# xmax_neopixel.net
KiCad netlist of a schematic drawn in EAGLE
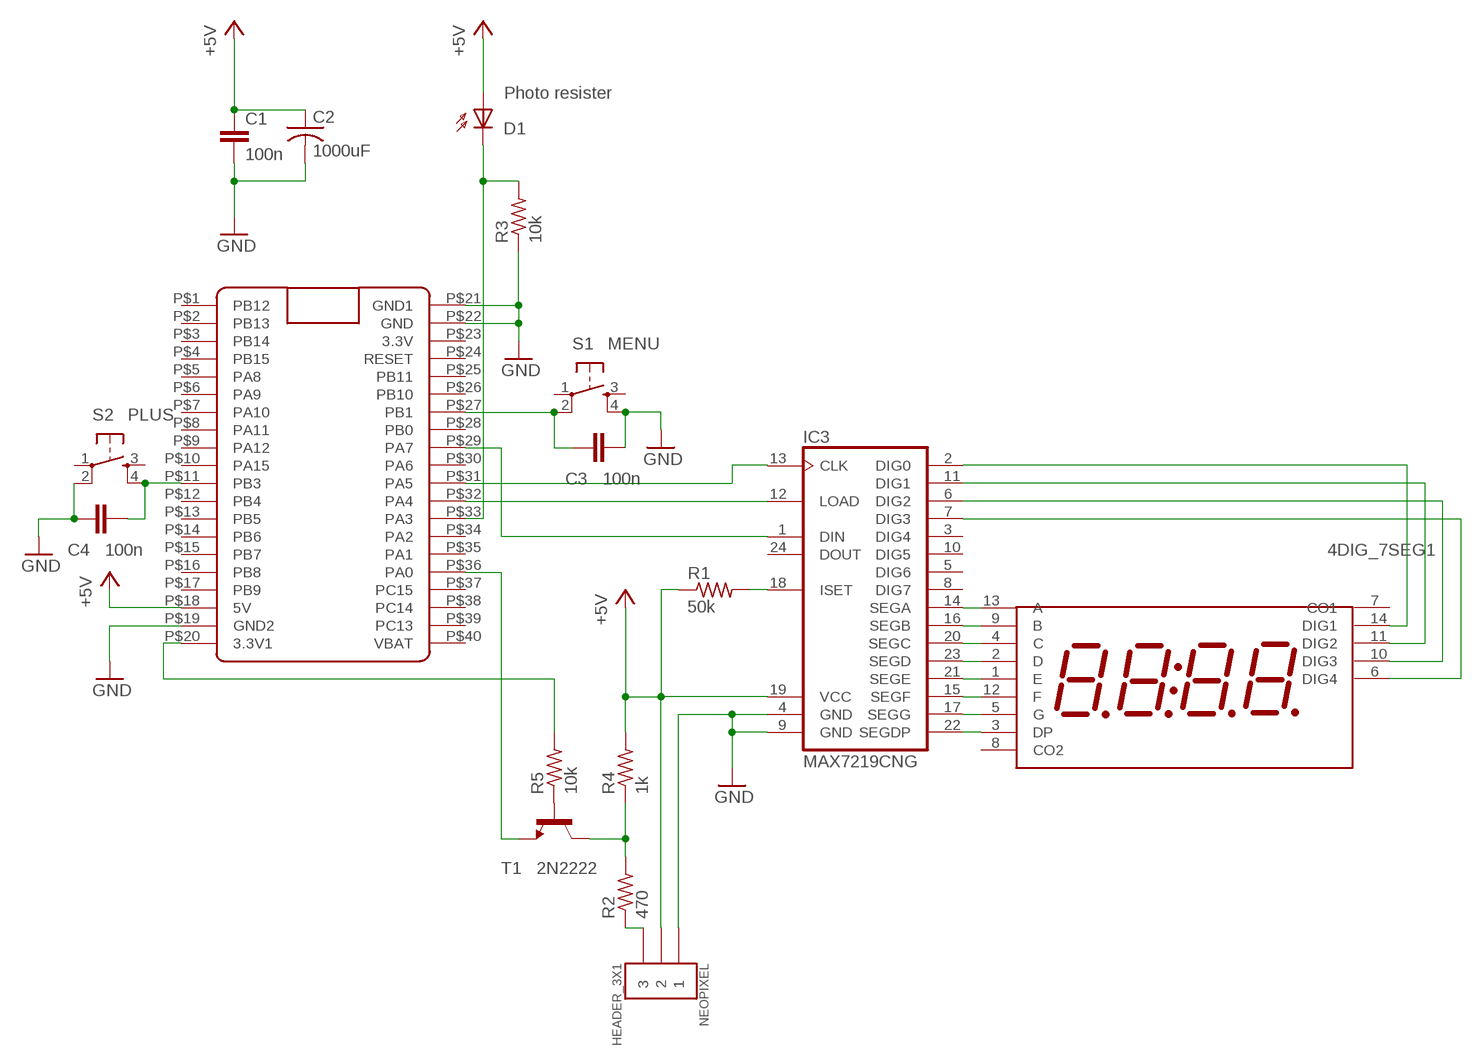
[diagram p0: schematic, sheet 1]

(export (version "E")
  (design (tool "Eeschema 10.0.6"))
  (components
    (comp (ref "4DIG_7SEG1")
      (value "4DIG_7SEG")
      (footprint "eagle-import:4DIG_7SEG")
      (libsource (lib "eagle-import") (part "4DIG_7SEG"))
    )
    (comp (ref "C1")
      (value "100n")
      (footprint "eagle-import:C025-024X044")
      (libsource (lib "eagle-import") (part "C-EU025-024X044"))
    )
    (comp (ref "C2")
      (value "1000uF")
      (footprint "eagle-import:C025-024X044")
      (libsource (lib "eagle-import") (part "C-US025-024X044"))
    )
    (comp (ref "C3")
      (value "100n")
      (footprint "eagle-import:C025-024X044")
      (libsource (lib "eagle-import") (part "C-EU025-024X044"))
    )
    (comp (ref "C4")
      (value "100n")
      (footprint "eagle-import:C025-024X044")
      (libsource (lib "eagle-import") (part "C-EU025-024X044"))
    )
    (comp (ref "D1")
      (value "Photo resister")
      (footprint "eagle-import:BPW32")
      (libsource (lib "eagle-import") (part "BPW32"))
    )
    (comp (ref "IC3")
      (value "MAX7219CNG")
      (footprint "eagle-import:DIL24-3")
      (fields (field (name "MF") "MAXIM"))
      (libsource (lib "eagle-import") (part "MAX7219CNG"))
    )
    (comp (ref "NEOPIXEL")
      (value "HEADER_3X1")
      (footprint "eagle-import:HDRV3W64P254_1X3_762X254X900B_NO_SILK")
      (libsource (lib "eagle-import") (part "HEADER_3X1"))
    )
    (comp (ref "R1")
      (value "50k")
      (footprint "eagle-import:0204_5")
      (libsource (lib "eagle-import") (part "R-US_0204/5"))
    )
    (comp (ref "R2")
      (value "470")
      (footprint "eagle-import:0204_5")
      (libsource (lib "eagle-import") (part "R-US_0204/5"))
    )
    (comp (ref "R3")
      (value "10k")
      (footprint "eagle-import:0204_5")
      (libsource (lib "eagle-import") (part "R-US_0204/5"))
    )
    (comp (ref "R4")
      (value "1k")
      (footprint "eagle-import:0204_5")
      (libsource (lib "eagle-import") (part "R-US_0204/5"))
    )
    (comp (ref "R5")
      (value "10k")
      (footprint "eagle-import:0204_5")
      (libsource (lib "eagle-import") (part "R-US_0204/5"))
    )
    (comp (ref "S1")
      (value "MENU")
      (footprint "eagle-import:TACTILE-PTH")
      (libsource (lib "eagle-import") (part "TAC_SWITCHPTH"))
    )
    (comp (ref "S2")
      (value "PLUS")
      (footprint "eagle-import:TACTILE-PTH")
      (libsource (lib "eagle-import") (part "TAC_SWITCHPTH"))
    )
    (comp (ref "T1")
      (value "2N2222")
      (footprint "eagle-import:TO92-EBC-OVAL")
      (libsource (lib "eagle-import") (part "2N2222"))
    )
    (comp (ref "U$2")
      (value "BLUE_PILL")
      (footprint "eagle-import:BLUE_PILL")
      (libsource (lib "eagle-import") (part "BLUE_PILL"))
    )
  )
  (nets
    (net (code "1") (name "+5V") (class "Default")
      (node (ref "C1") (pin "1") (pinfunction "1_1") (pintype "passive"))
      (node (ref "C2") (pin "1") (pinfunction "1_1") (pintype "passive"))
      (node (ref "D1") (pin "A") (pinfunction "A_A") (pintype "passive"))
      (node (ref "IC3") (pin "19") (pinfunction "VCC_19") (pintype "power_in"))
      (node (ref "NEOPIXEL") (pin "P$2") (pinfunction "2_P$2") (pintype "bidirectional"))
      (node (ref "R1") (pin "1") (pinfunction "1_1") (pintype "passive"))
      (node (ref "R4") (pin "2") (pinfunction "2_2") (pintype "passive"))
      (node (ref "U$2") (pin "P$18") (pinfunction "5V_P$18") (pintype "bidirectional"))
    )
    (net (code "2") (name "GND") (class "Default")
      (node (ref "C1") (pin "2") (pinfunction "2_2") (pintype "passive"))
      (node (ref "C2") (pin "2") (pinfunction "2_2") (pintype "passive"))
      (node (ref "C3") (pin "2") (pinfunction "2_2") (pintype "passive"))
      (node (ref "C4") (pin "1") (pinfunction "1_1") (pintype "passive"))
      (node (ref "IC3") (pin "4") (pinfunction "GND_4") (pintype "power_in"))
      (node (ref "IC3") (pin "9") (pinfunction "GND_9") (pintype "power_in"))
      (node (ref "NEOPIXEL") (pin "P$1") (pinfunction "1_P$1") (pintype "bidirectional"))
      (node (ref "R3") (pin "1") (pinfunction "1_1") (pintype "passive"))
      (node (ref "S1") (pin "4") (pinfunction "4_4") (pintype "passive"))
      (node (ref "S2") (pin "2") (pinfunction "2_2") (pintype "passive"))
      (node (ref "U$2") (pin "P$19") (pinfunction "GND2_P$19") (pintype "bidirectional"))
      (node (ref "U$2") (pin "P$21") (pinfunction "GND1_P$21") (pintype "power_in"))
      (node (ref "U$2") (pin "P$22") (pinfunction "GND_P$22") (pintype "bidirectional"))
    )
    (net (code "3") (name "Net-(4DIG_7SEG1-A)") (class "Default")
      (node (ref "4DIG_7SEG1") (pin "13") (pinfunction "A_13") (pintype "bidirectional"))
      (node (ref "IC3") (pin "14") (pinfunction "SEGA_14") (pintype "output"))
    )
    (net (code "4") (name "Net-(4DIG_7SEG1-B)") (class "Default")
      (node (ref "4DIG_7SEG1") (pin "9") (pinfunction "B_9") (pintype "bidirectional"))
      (node (ref "IC3") (pin "16") (pinfunction "SEGB_16") (pintype "output"))
    )
    (net (code "5") (name "Net-(4DIG_7SEG1-C)") (class "Default")
      (node (ref "4DIG_7SEG1") (pin "4") (pinfunction "C_4") (pintype "bidirectional"))
      (node (ref "IC3") (pin "20") (pinfunction "SEGC_20") (pintype "output"))
    )
    (net (code "6") (name "Net-(4DIG_7SEG1-D)") (class "Default")
      (node (ref "4DIG_7SEG1") (pin "2") (pinfunction "D_2") (pintype "bidirectional"))
      (node (ref "IC3") (pin "23") (pinfunction "SEGD_23") (pintype "output"))
    )
    (net (code "7") (name "Net-(4DIG_7SEG1-DIG1)") (class "Default")
      (node (ref "4DIG_7SEG1") (pin "14") (pinfunction "DIG1_14") (pintype "bidirectional"))
      (node (ref "IC3") (pin "2") (pinfunction "DIG0_2") (pintype "output"))
    )
    (net (code "8") (name "Net-(4DIG_7SEG1-DIG2)") (class "Default")
      (node (ref "4DIG_7SEG1") (pin "11") (pinfunction "DIG2_11") (pintype "bidirectional"))
      (node (ref "IC3") (pin "11") (pinfunction "DIG1_11") (pintype "output"))
    )
    (net (code "9") (name "Net-(4DIG_7SEG1-DIG3)") (class "Default")
      (node (ref "4DIG_7SEG1") (pin "10") (pinfunction "DIG3_10") (pintype "bidirectional"))
      (node (ref "IC3") (pin "6") (pinfunction "DIG2_6") (pintype "output"))
    )
    (net (code "10") (name "Net-(4DIG_7SEG1-DIG4)") (class "Default")
      (node (ref "4DIG_7SEG1") (pin "6") (pinfunction "DIG4_6") (pintype "bidirectional"))
      (node (ref "IC3") (pin "7") (pinfunction "DIG3_7") (pintype "output"))
    )
    (net (code "11") (name "Net-(4DIG_7SEG1-DP)") (class "Default")
      (node (ref "4DIG_7SEG1") (pin "3") (pinfunction "DP_3") (pintype "bidirectional"))
      (node (ref "IC3") (pin "22") (pinfunction "SEGDP_22") (pintype "output"))
    )
    (net (code "12") (name "Net-(4DIG_7SEG1-E)") (class "Default")
      (node (ref "4DIG_7SEG1") (pin "1") (pinfunction "E_1") (pintype "bidirectional"))
      (node (ref "IC3") (pin "21") (pinfunction "SEGE_21") (pintype "output"))
    )
    (net (code "13") (name "Net-(4DIG_7SEG1-F)") (class "Default")
      (node (ref "4DIG_7SEG1") (pin "12") (pinfunction "F_12") (pintype "bidirectional"))
      (node (ref "IC3") (pin "15") (pinfunction "SEGF_15") (pintype "output"))
    )
    (net (code "14") (name "Net-(4DIG_7SEG1-G)") (class "Default")
      (node (ref "4DIG_7SEG1") (pin "5") (pinfunction "G_5") (pintype "bidirectional"))
      (node (ref "IC3") (pin "17") (pinfunction "SEGG_17") (pintype "output"))
    )
    (net (code "15") (name "Net-(D1-C)") (class "Default")
      (node (ref "D1") (pin "K") (pinfunction "C_K") (pintype "passive"))
      (node (ref "R3") (pin "2") (pinfunction "2_2") (pintype "passive"))
      (node (ref "U$2") (pin "P$33") (pinfunction "PA3_P$33") (pintype "bidirectional"))
    )
    (net (code "16") (name "Net-(IC3-CLK)") (class "Default")
      (node (ref "IC3") (pin "13") (pinfunction "CLK_13") (pintype "input"))
      (node (ref "U$2") (pin "P$31") (pinfunction "PA5_P$31") (pintype "bidirectional"))
    )
    (net (code "17") (name "Net-(IC3-DIN)") (class "Default")
      (node (ref "IC3") (pin "1") (pinfunction "DIN_1") (pintype "input"))
      (node (ref "U$2") (pin "P$29") (pinfunction "PA7_P$29") (pintype "bidirectional"))
    )
    (net (code "18") (name "Net-(IC3-ISET)") (class "Default")
      (node (ref "IC3") (pin "18") (pinfunction "ISET_18") (pintype "input"))
      (node (ref "R1") (pin "2") (pinfunction "2_2") (pintype "passive"))
    )
    (net (code "19") (name "Net-(IC3-LOAD)") (class "Default")
      (node (ref "IC3") (pin "12") (pinfunction "LOAD_12") (pintype "input"))
      (node (ref "U$2") (pin "P$32") (pinfunction "PA4_P$32") (pintype "bidirectional"))
    )
    (net (code "20") (name "Net-(NEOPIXEL-3)") (class "Default")
      (node (ref "NEOPIXEL") (pin "P$3") (pinfunction "3_P$3") (pintype "bidirectional"))
      (node (ref "R2") (pin "1") (pinfunction "1_1") (pintype "passive"))
    )
    (net (code "21") (name "Net-(R2-Pad2)") (class "Default")
      (node (ref "R2") (pin "2") (pinfunction "2_2") (pintype "passive"))
      (node (ref "R4") (pin "1") (pinfunction "1_1") (pintype "passive"))
      (node (ref "T1") (pin "C") (pinfunction "C_C") (pintype "passive"))
    )
    (net (code "22") (name "Net-(R5-Pad1)") (class "Default")
      (node (ref "R5") (pin "1") (pinfunction "1_1") (pintype "passive"))
      (node (ref "T1") (pin "B") (pinfunction "B_B") (pintype "passive"))
    )
    (net (code "23") (name "Net-(U$2-3.3V1)") (class "Default")
      (node (ref "R5") (pin "2") (pinfunction "2_2") (pintype "passive"))
      (node (ref "U$2") (pin "P$20") (pinfunction "3.3V1_P$20") (pintype "bidirectional"))
    )
    (net (code "24") (name "Net-(U$2-PA0)") (class "Default")
      (node (ref "T1") (pin "E") (pinfunction "E_E") (pintype "passive"))
      (node (ref "U$2") (pin "P$36") (pinfunction "PA0_P$36") (pintype "bidirectional"))
    )
    (net (code "25") (name "Net-(U$2-PB1)") (class "Default")
      (node (ref "C3") (pin "1") (pinfunction "1_1") (pintype "passive"))
      (node (ref "S1") (pin "2") (pinfunction "2_2") (pintype "passive"))
      (node (ref "U$2") (pin "P$27") (pinfunction "PB1_P$27") (pintype "bidirectional"))
    )
    (net (code "26") (name "Net-(U$2-PB3)") (class "Default")
      (node (ref "C4") (pin "2") (pinfunction "2_2") (pintype "passive"))
      (node (ref "S2") (pin "4") (pinfunction "4_4") (pintype "passive"))
      (node (ref "U$2") (pin "P$11") (pinfunction "PB3_P$11") (pintype "bidirectional"))
    )
    (net (code "27") (name "unconnected-(4DIG_7SEG1-CO1-Pad7)") (class "Default")
      (node (ref "4DIG_7SEG1") (pin "7") (pinfunction "CO1_7") (pintype "bidirectional"))
    )
    (net (code "28") (name "unconnected-(4DIG_7SEG1-CO2-Pad8)") (class "Default")
      (node (ref "4DIG_7SEG1") (pin "8") (pinfunction "CO2_8") (pintype "bidirectional"))
    )
    (net (code "29") (name "unconnected-(IC3-DIG4-Pad3)") (class "Default")
      (node (ref "IC3") (pin "3") (pinfunction "DIG4_3") (pintype "output"))
    )
    (net (code "30") (name "unconnected-(IC3-DIG5-Pad10)") (class "Default")
      (node (ref "IC3") (pin "10") (pinfunction "DIG5_10") (pintype "output"))
    )
    (net (code "31") (name "unconnected-(IC3-DIG6-Pad5)") (class "Default")
      (node (ref "IC3") (pin "5") (pinfunction "DIG6_5") (pintype "output"))
    )
    (net (code "32") (name "unconnected-(IC3-DIG7-Pad8)") (class "Default")
      (node (ref "IC3") (pin "8") (pinfunction "DIG7_8") (pintype "output"))
    )
    (net (code "33") (name "unconnected-(IC3-DOUT-Pad24)") (class "Default")
      (node (ref "IC3") (pin "24") (pinfunction "DOUT_24") (pintype "output"))
    )
    (net (code "34") (name "unconnected-(S1-Pad1)") (class "Default")
      (node (ref "S1") (pin "1") (pinfunction "1_1") (pintype "passive"))
    )
    (net (code "35") (name "unconnected-(S1-Pad3)") (class "Default")
      (node (ref "S1") (pin "3") (pinfunction "3_3") (pintype "passive"))
    )
    (net (code "36") (name "unconnected-(S2-Pad1)") (class "Default")
      (node (ref "S2") (pin "1") (pinfunction "1_1") (pintype "passive"))
    )
    (net (code "37") (name "unconnected-(S2-Pad3)") (class "Default")
      (node (ref "S2") (pin "3") (pinfunction "3_3") (pintype "passive"))
    )
    (net (code "38") (name "unconnected-(U$2-3.3V-PadP$23)") (class "Default")
      (node (ref "U$2") (pin "P$23") (pinfunction "3.3V_P$23") (pintype "bidirectional"))
    )
    (net (code "39") (name "unconnected-(U$2-PA1-PadP$35)") (class "Default")
      (node (ref "U$2") (pin "P$35") (pinfunction "PA1_P$35") (pintype "bidirectional"))
    )
    (net (code "40") (name "unconnected-(U$2-PA2-PadP$34)") (class "Default")
      (node (ref "U$2") (pin "P$34") (pinfunction "PA2_P$34") (pintype "bidirectional"))
    )
    (net (code "41") (name "unconnected-(U$2-PA6-PadP$30)") (class "Default")
      (node (ref "U$2") (pin "P$30") (pinfunction "PA6_P$30") (pintype "bidirectional"))
    )
    (net (code "42") (name "unconnected-(U$2-PA8-PadP$5)") (class "Default")
      (node (ref "U$2") (pin "P$5") (pinfunction "PA8_P$5") (pintype "bidirectional"))
    )
    (net (code "43") (name "unconnected-(U$2-PA9-PadP$6)") (class "Default")
      (node (ref "U$2") (pin "P$6") (pinfunction "PA9_P$6") (pintype "bidirectional"))
    )
    (net (code "44") (name "unconnected-(U$2-PA10-PadP$7)") (class "Default")
      (node (ref "U$2") (pin "P$7") (pinfunction "PA10_P$7") (pintype "bidirectional"))
    )
    (net (code "45") (name "unconnected-(U$2-PA11-PadP$8)") (class "Default")
      (node (ref "U$2") (pin "P$8") (pinfunction "PA11_P$8") (pintype "bidirectional"))
    )
    (net (code "46") (name "unconnected-(U$2-PA12-PadP$9)") (class "Default")
      (node (ref "U$2") (pin "P$9") (pinfunction "PA12_P$9") (pintype "bidirectional"))
    )
    (net (code "47") (name "unconnected-(U$2-PA15-PadP$10)") (class "Default")
      (node (ref "U$2") (pin "P$10") (pinfunction "PA15_P$10") (pintype "bidirectional"))
    )
    (net (code "48") (name "unconnected-(U$2-PB0-PadP$28)") (class "Default")
      (node (ref "U$2") (pin "P$28") (pinfunction "PB0_P$28") (pintype "bidirectional"))
    )
    (net (code "49") (name "unconnected-(U$2-PB4-PadP$12)") (class "Default")
      (node (ref "U$2") (pin "P$12") (pinfunction "PB4_P$12") (pintype "bidirectional"))
    )
    (net (code "50") (name "unconnected-(U$2-PB5-PadP$13)") (class "Default")
      (node (ref "U$2") (pin "P$13") (pinfunction "PB5_P$13") (pintype "bidirectional"))
    )
    (net (code "51") (name "unconnected-(U$2-PB6-PadP$14)") (class "Default")
      (node (ref "U$2") (pin "P$14") (pinfunction "PB6_P$14") (pintype "bidirectional"))
    )
    (net (code "52") (name "unconnected-(U$2-PB7-PadP$15)") (class "Default")
      (node (ref "U$2") (pin "P$15") (pinfunction "PB7_P$15") (pintype "bidirectional"))
    )
    (net (code "53") (name "unconnected-(U$2-PB8-PadP$16)") (class "Default")
      (node (ref "U$2") (pin "P$16") (pinfunction "PB8_P$16") (pintype "bidirectional"))
    )
    (net (code "54") (name "unconnected-(U$2-PB9-PadP$17)") (class "Default")
      (node (ref "U$2") (pin "P$17") (pinfunction "PB9_P$17") (pintype "bidirectional"))
    )
    (net (code "55") (name "unconnected-(U$2-PB10-PadP$26)") (class "Default")
      (node (ref "U$2") (pin "P$26") (pinfunction "PB10_P$26") (pintype "bidirectional"))
    )
    (net (code "56") (name "unconnected-(U$2-PB11-PadP$25)") (class "Default")
      (node (ref "U$2") (pin "P$25") (pinfunction "PB11_P$25") (pintype "bidirectional"))
    )
    (net (code "57") (name "unconnected-(U$2-PB12-PadP$1)") (class "Default")
      (node (ref "U$2") (pin "P$1") (pinfunction "PB12_P$1") (pintype "bidirectional"))
    )
    (net (code "58") (name "unconnected-(U$2-PB13-PadP$2)") (class "Default")
      (node (ref "U$2") (pin "P$2") (pinfunction "PB13_P$2") (pintype "bidirectional"))
    )
    (net (code "59") (name "unconnected-(U$2-PB14-PadP$3)") (class "Default")
      (node (ref "U$2") (pin "P$3") (pinfunction "PB14_P$3") (pintype "bidirectional"))
    )
    (net (code "60") (name "unconnected-(U$2-PB15-PadP$4)") (class "Default")
      (node (ref "U$2") (pin "P$4") (pinfunction "PB15_P$4") (pintype "bidirectional"))
    )
    (net (code "61") (name "unconnected-(U$2-PC13-PadP$39)") (class "Default")
      (node (ref "U$2") (pin "P$39") (pinfunction "PC13_P$39") (pintype "bidirectional"))
    )
    (net (code "62") (name "unconnected-(U$2-PC14-PadP$38)") (class "Default")
      (node (ref "U$2") (pin "P$38") (pinfunction "PC14_P$38") (pintype "bidirectional"))
    )
    (net (code "63") (name "unconnected-(U$2-PC15-PadP$37)") (class "Default")
      (node (ref "U$2") (pin "P$37") (pinfunction "PC15_P$37") (pintype "bidirectional"))
    )
    (net (code "64") (name "unconnected-(U$2-RESET-PadP$24)") (class "Default")
      (node (ref "U$2") (pin "P$24") (pinfunction "RESET_P$24") (pintype "bidirectional"))
    )
    (net (code "65") (name "unconnected-(U$2-VBAT-PadP$40)") (class "Default")
      (node (ref "U$2") (pin "P$40") (pinfunction "VBAT_P$40") (pintype "bidirectional"))
    )
  )
)
